# Medir-220.net
KiCad netlist of a schematic drawn in EAGLE
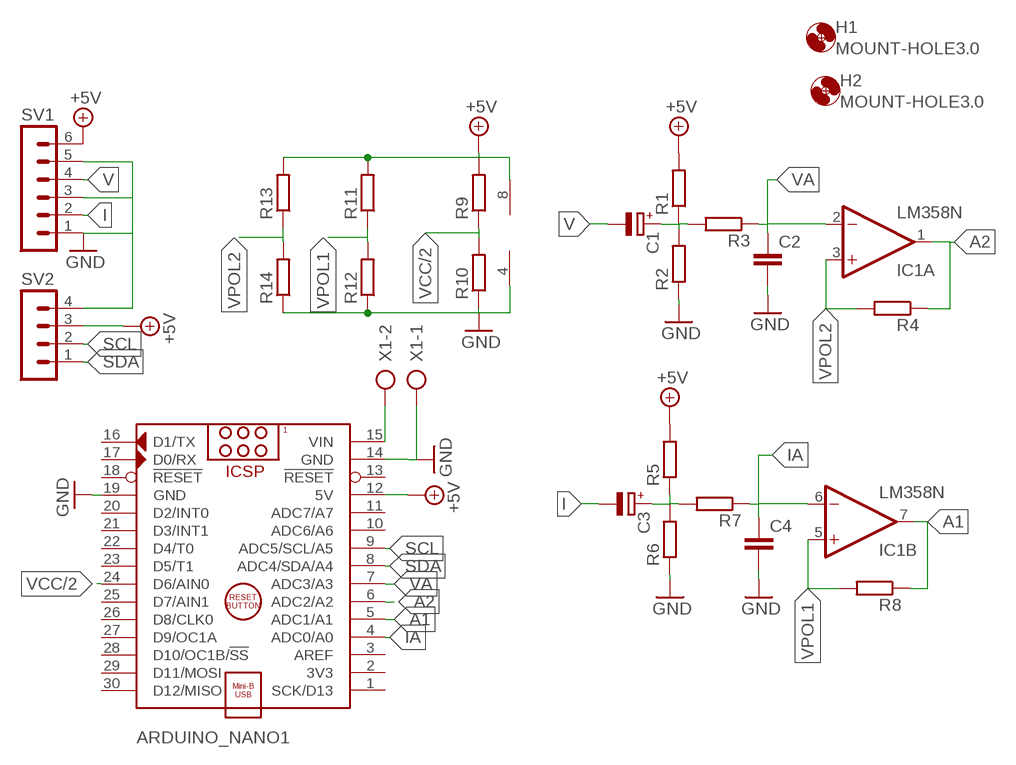
[diagram p0: schematic, sheet 1]

(export (version "E")
  (design (tool "Eeschema 10.0.6"))
  (components
    (comp (ref "ARDUINO_NANO1")
      (value "ARDUINO_NANO")
      (footprint "eagle-import:ARDUINO_NANO")
      (libsource (lib "eagle-import") (part "ARDUINO_NANO"))
    )
    (comp (ref "C1")
      (value "CPOL-EUE2.5-5")
      (footprint "eagle-import:E2,5-5")
      (libsource (lib "eagle-import") (part "CPOL-EUE2.5-5"))
    )
    (comp (ref "C2")
      (value "C-EU050-025X075")
      (footprint "eagle-import:C050-025X075")
      (libsource (lib "eagle-import") (part "C-EU050-025X075"))
    )
    (comp (ref "C3")
      (value "CPOL-EUE2.5-5")
      (footprint "eagle-import:E2,5-5")
      (libsource (lib "eagle-import") (part "CPOL-EUE2.5-5"))
    )
    (comp (ref "C4")
      (value "C-EU050-025X075")
      (footprint "eagle-import:C050-025X075")
      (libsource (lib "eagle-import") (part "C-EU050-025X075"))
    )
    (comp (ref "H1")
      (value "MOUNT-HOLE3.0")
      (footprint "eagle-import:3,0")
      (libsource (lib "eagle-import") (part "MOUNT-HOLE3.0"))
    )
    (comp (ref "H2")
      (value "MOUNT-HOLE3.0")
      (footprint "eagle-import:3,0")
      (libsource (lib "eagle-import") (part "MOUNT-HOLE3.0"))
    )
    (comp (ref "IC1")
      (value "LM358N")
      (footprint "eagle-import:DIL08")
      (libsource (lib "eagle-import") (part "LM358N"))
    )
    (comp (ref "R1")
      (value "R-EU_0207/7")
      (footprint "eagle-import:0207_7")
      (libsource (lib "eagle-import") (part "resistor_R-EU_0207/7"))
    )
    (comp (ref "R2")
      (value "R-EU_0207/7")
      (footprint "eagle-import:0207_7")
      (libsource (lib "eagle-import") (part "resistor_R-EU_0207/7"))
    )
    (comp (ref "R3")
      (value "R-EU_0207/7")
      (footprint "eagle-import:0207_7")
      (libsource (lib "eagle-import") (part "resistor_R-EU_0207/7"))
    )
    (comp (ref "R4")
      (value "R-EU_0207/7")
      (footprint "eagle-import:0207_7")
      (libsource (lib "eagle-import") (part "resistor_R-EU_0207/7"))
    )
    (comp (ref "R5")
      (value "R-EU_0207/7")
      (footprint "eagle-import:0207_7")
      (libsource (lib "eagle-import") (part "resistor_R-EU_0207/7"))
    )
    (comp (ref "R6")
      (value "R-EU_0207/7")
      (footprint "eagle-import:0207_7")
      (libsource (lib "eagle-import") (part "resistor_R-EU_0207/7"))
    )
    (comp (ref "R7")
      (value "R-EU_0207/7")
      (footprint "eagle-import:0207_7")
      (libsource (lib "eagle-import") (part "resistor_R-EU_0207/7"))
    )
    (comp (ref "R8")
      (value "R-EU_0207/7")
      (footprint "eagle-import:0207_7")
      (libsource (lib "eagle-import") (part "resistor_R-EU_0207/7"))
    )
    (comp (ref "R9")
      (value "R-EU_0207/10")
      (footprint "eagle-import:0207_10")
      (libsource (lib "eagle-import") (part "R-EU_0207/10"))
    )
    (comp (ref "R10")
      (value "R-EU_0207/10")
      (footprint "eagle-import:0207_10")
      (libsource (lib "eagle-import") (part "R-EU_0207/10"))
    )
    (comp (ref "R11")
      (value "R-EU_0207/7")
      (footprint "eagle-import:0207_7")
      (libsource (lib "eagle-import") (part "resistor_R-EU_0207/7"))
    )
    (comp (ref "R12")
      (value "R-EU_0207/7")
      (footprint "eagle-import:0207_7")
      (libsource (lib "eagle-import") (part "resistor_R-EU_0207/7"))
    )
    (comp (ref "R13")
      (value "R-EU_0207/7")
      (footprint "eagle-import:0207_7")
      (libsource (lib "eagle-import") (part "resistor_R-EU_0207/7"))
    )
    (comp (ref "R14")
      (value "R-EU_0207/7")
      (footprint "eagle-import:0207_7")
      (libsource (lib "eagle-import") (part "resistor_R-EU_0207/7"))
    )
    (comp (ref "SV1")
      (value "MA06-1")
      (footprint "eagle-import:MA06-1")
      (libsource (lib "eagle-import") (part "MA06-1"))
    )
    (comp (ref "SV2")
      (value "MA04-1")
      (footprint "eagle-import:MA04-1")
      (libsource (lib "eagle-import") (part "MA04-1"))
    )
    (comp (ref "X1")
      (value "AK500/2")
      (footprint "eagle-import:AK500_2")
      (libsource (lib "eagle-import") (part "AK500/2"))
    )
  )
  (nets
    (net (code "1") (name "+5V") (class "Default")
      (node (ref "ARDUINO_NANO1") (pin "12") (pinfunction "5V_12") (pintype "power_in"))
      (node (ref "IC1") (pin "8") (pinfunction "V+_8") (pintype "power_in"))
      (node (ref "R1") (pin "2") (pinfunction "2_2") (pintype "passive"))
      (node (ref "R11") (pin "2") (pinfunction "2_2") (pintype "passive"))
      (node (ref "R13") (pin "2") (pinfunction "2_2") (pintype "passive"))
      (node (ref "R5") (pin "2") (pinfunction "2_2") (pintype "passive"))
      (node (ref "R9") (pin "2") (pinfunction "2_2") (pintype "passive"))
      (node (ref "SV1") (pin "6") (pinfunction "6_6") (pintype "passive"))
      (node (ref "SV2") (pin "3") (pinfunction "3_3") (pintype "passive"))
    )
    (net (code "2") (name "A1") (class "Default")
      (node (ref "ARDUINO_NANO1") (pin "5") (pinfunction "ADC1/A1_5") (pintype "bidirectional"))
      (node (ref "IC1") (pin "7") (pinfunction "OUT_7") (pintype "output"))
      (node (ref "R8") (pin "1") (pinfunction "1_1") (pintype "passive"))
    )
    (net (code "3") (name "A2") (class "Default")
      (node (ref "ARDUINO_NANO1") (pin "6") (pinfunction "ADC2/A2_6") (pintype "bidirectional"))
      (node (ref "IC1") (pin "1") (pinfunction "OUT_1") (pintype "output"))
      (node (ref "R4") (pin "1") (pinfunction "1_1") (pintype "passive"))
    )
    (net (code "4") (name "GND") (class "Default")
      (node (ref "ARDUINO_NANO1") (pin "14") (pinfunction "GND_14") (pintype "power_in"))
      (node (ref "ARDUINO_NANO1") (pin "19") (pinfunction "GND_19") (pintype "power_in"))
      (node (ref "C2") (pin "2") (pinfunction "2_2") (pintype "passive"))
      (node (ref "C4") (pin "2") (pinfunction "2_2") (pintype "passive"))
      (node (ref "IC1") (pin "4") (pinfunction "V-_4") (pintype "power_in"))
      (node (ref "R10") (pin "1") (pinfunction "1_1") (pintype "passive"))
      (node (ref "R12") (pin "1") (pinfunction "1_1") (pintype "passive"))
      (node (ref "R14") (pin "1") (pinfunction "1_1") (pintype "passive"))
      (node (ref "R2") (pin "1") (pinfunction "1_1") (pintype "passive"))
      (node (ref "R6") (pin "1") (pinfunction "1_1") (pintype "passive"))
      (node (ref "SV1") (pin "1") (pinfunction "1_1") (pintype "passive"))
      (node (ref "SV1") (pin "3") (pinfunction "3_3") (pintype "passive"))
      (node (ref "SV1") (pin "5") (pinfunction "5_5") (pintype "passive"))
      (node (ref "SV2") (pin "4") (pinfunction "4_4") (pintype "passive"))
      (node (ref "X1") (pin "1") (pinfunction "KL_1") (pintype "passive"))
    )
    (net (code "5") (name "I") (class "Default")
      (node (ref "C3") (pin "-") (pinfunction "-_-") (pintype "passive"))
      (node (ref "SV1") (pin "2") (pinfunction "2_2") (pintype "passive"))
    )
    (net (code "6") (name "IA") (class "Default")
      (node (ref "ARDUINO_NANO1") (pin "4") (pinfunction "ADC0/A0_4") (pintype "bidirectional"))
      (node (ref "C4") (pin "1") (pinfunction "1_1") (pintype "passive"))
      (node (ref "IC1") (pin "6") (pinfunction "-IN_6") (pintype "input"))
      (node (ref "R7") (pin "1") (pinfunction "1_1") (pintype "passive"))
    )
    (net (code "7") (name "Net-(ARDUINO_NANO1-VIN)") (class "Default")
      (node (ref "ARDUINO_NANO1") (pin "15") (pinfunction "VIN_15") (pintype "power_in"))
      (node (ref "X1") (pin "2") (pinfunction "KL_2") (pintype "passive"))
    )
    (net (code "8") (name "Net-(C1-Pad+)") (class "Default")
      (node (ref "C1") (pin "+") (pinfunction "+_+") (pintype "passive"))
      (node (ref "R1") (pin "1") (pinfunction "1_1") (pintype "passive"))
      (node (ref "R2") (pin "2") (pinfunction "2_2") (pintype "passive"))
      (node (ref "R3") (pin "2") (pinfunction "2_2") (pintype "passive"))
    )
    (net (code "9") (name "Net-(C3-Pad+)") (class "Default")
      (node (ref "C3") (pin "+") (pinfunction "+_+") (pintype "passive"))
      (node (ref "R5") (pin "1") (pinfunction "1_1") (pintype "passive"))
      (node (ref "R6") (pin "2") (pinfunction "2_2") (pintype "passive"))
      (node (ref "R7") (pin "2") (pinfunction "2_2") (pintype "passive"))
    )
    (net (code "10") (name "SCL") (class "Default")
      (node (ref "ARDUINO_NANO1") (pin "9") (pinfunction "ADC5/SCL/A5_9") (pintype "bidirectional"))
      (node (ref "SV2") (pin "2") (pinfunction "2_2") (pintype "passive"))
    )
    (net (code "11") (name "SDA") (class "Default")
      (node (ref "ARDUINO_NANO1") (pin "8") (pinfunction "ADC4/SDA/A4_8") (pintype "bidirectional"))
      (node (ref "SV2") (pin "1") (pinfunction "1_1") (pintype "passive"))
    )
    (net (code "12") (name "V") (class "Default")
      (node (ref "C1") (pin "-") (pinfunction "-_-") (pintype "passive"))
      (node (ref "SV1") (pin "4") (pinfunction "4_4") (pintype "passive"))
    )
    (net (code "13") (name "VA") (class "Default")
      (node (ref "ARDUINO_NANO1") (pin "7") (pinfunction "ADC3/A3_7") (pintype "bidirectional"))
      (node (ref "C2") (pin "1") (pinfunction "1_1") (pintype "passive"))
      (node (ref "IC1") (pin "2") (pinfunction "-IN_2") (pintype "input"))
      (node (ref "R3") (pin "1") (pinfunction "1_1") (pintype "passive"))
    )
    (net (code "14") (name "VCC{slash}2") (class "Default")
      (node (ref "ARDUINO_NANO1") (pin "24") (pinfunction "D6/AIN0_24") (pintype "bidirectional"))
      (node (ref "R10") (pin "2") (pinfunction "2_2") (pintype "passive"))
      (node (ref "R9") (pin "1") (pinfunction "1_1") (pintype "passive"))
    )
    (net (code "15") (name "VPOL1") (class "Default")
      (node (ref "IC1") (pin "5") (pinfunction "+IN_5") (pintype "input"))
      (node (ref "R11") (pin "1") (pinfunction "1_1") (pintype "passive"))
      (node (ref "R12") (pin "2") (pinfunction "2_2") (pintype "passive"))
      (node (ref "R8") (pin "2") (pinfunction "2_2") (pintype "passive"))
    )
    (net (code "16") (name "VPOL2") (class "Default")
      (node (ref "IC1") (pin "3") (pinfunction "+IN_3") (pintype "input"))
      (node (ref "R13") (pin "1") (pinfunction "1_1") (pintype "passive"))
      (node (ref "R14") (pin "2") (pinfunction "2_2") (pintype "passive"))
      (node (ref "R4") (pin "2") (pinfunction "2_2") (pintype "passive"))
    )
    (net (code "17") (name "unconnected-(ARDUINO_NANO1-3V3-Pad2)") (class "Default")
      (node (ref "ARDUINO_NANO1") (pin "2") (pinfunction "3V3_2") (pintype "output"))
    )
    (net (code "18") (name "unconnected-(ARDUINO_NANO1-ADC6{slash}A6-Pad10)") (class "Default")
      (node (ref "ARDUINO_NANO1") (pin "10") (pinfunction "ADC6/A6_10") (pintype "bidirectional"))
    )
    (net (code "19") (name "unconnected-(ARDUINO_NANO1-ADC7{slash}A7-Pad11)") (class "Default")
      (node (ref "ARDUINO_NANO1") (pin "11") (pinfunction "ADC7/A7_11") (pintype "bidirectional"))
    )
    (net (code "20") (name "unconnected-(ARDUINO_NANO1-AREF-Pad3)") (class "Default")
      (node (ref "ARDUINO_NANO1") (pin "3") (pinfunction "AREF_3") (pintype "input"))
    )
    (net (code "21") (name "unconnected-(ARDUINO_NANO1-D0{slash}RX-Pad17)") (class "Default")
      (node (ref "ARDUINO_NANO1") (pin "17") (pinfunction "D0/RX_17") (pintype "bidirectional"))
    )
    (net (code "22") (name "unconnected-(ARDUINO_NANO1-D1{slash}TX-Pad16)") (class "Default")
      (node (ref "ARDUINO_NANO1") (pin "16") (pinfunction "D1/TX_16") (pintype "bidirectional"))
    )
    (net (code "23") (name "unconnected-(ARDUINO_NANO1-D2{slash}INT0-Pad20)") (class "Default")
      (node (ref "ARDUINO_NANO1") (pin "20") (pinfunction "D2/INT0_20") (pintype "bidirectional"))
    )
    (net (code "24") (name "unconnected-(ARDUINO_NANO1-D3{slash}INT1-Pad21)") (class "Default")
      (node (ref "ARDUINO_NANO1") (pin "21") (pinfunction "D3/INT1_21") (pintype "bidirectional"))
    )
    (net (code "25") (name "unconnected-(ARDUINO_NANO1-D4{slash}T0-Pad22)") (class "Default")
      (node (ref "ARDUINO_NANO1") (pin "22") (pinfunction "D4/T0_22") (pintype "bidirectional"))
    )
    (net (code "26") (name "unconnected-(ARDUINO_NANO1-D5{slash}T1-Pad23)") (class "Default")
      (node (ref "ARDUINO_NANO1") (pin "23") (pinfunction "D5/T1_23") (pintype "bidirectional"))
    )
    (net (code "27") (name "unconnected-(ARDUINO_NANO1-D7{slash}AIN1-Pad25)") (class "Default")
      (node (ref "ARDUINO_NANO1") (pin "25") (pinfunction "D7/AIN1_25") (pintype "bidirectional"))
    )
    (net (code "28") (name "unconnected-(ARDUINO_NANO1-D8{slash}CLK0-Pad26)") (class "Default")
      (node (ref "ARDUINO_NANO1") (pin "26") (pinfunction "D8/CLK0_26") (pintype "bidirectional"))
    )
    (net (code "29") (name "unconnected-(ARDUINO_NANO1-D9{slash}OC1A-Pad27)") (class "Default")
      (node (ref "ARDUINO_NANO1") (pin "27") (pinfunction "D9/OC1A_27") (pintype "bidirectional"))
    )
    (net (code "30") (name "unconnected-(ARDUINO_NANO1-D10{slash}OC1B{slash}~{SS}-Pad28)") (class "Default")
      (node (ref "ARDUINO_NANO1") (pin "28") (pinfunction "D10/OC1B/~{SS}_28") (pintype "bidirectional"))
    )
    (net (code "31") (name "unconnected-(ARDUINO_NANO1-D11{slash}MOSI-Pad29)") (class "Default")
      (node (ref "ARDUINO_NANO1") (pin "29") (pinfunction "D11/MOSI_29") (pintype "bidirectional"))
    )
    (net (code "32") (name "unconnected-(ARDUINO_NANO1-D12{slash}MISO-Pad30)") (class "Default")
      (node (ref "ARDUINO_NANO1") (pin "30") (pinfunction "D12/MISO_30") (pintype "bidirectional"))
    )
    (net (code "33") (name "unconnected-(ARDUINO_NANO1-SCK{slash}D13-Pad1)") (class "Default")
      (node (ref "ARDUINO_NANO1") (pin "1") (pinfunction "SCK/D13_1") (pintype "bidirectional"))
    )
    (net (code "34") (name "unconnected-(ARDUINO_NANO1-~{RESET}-Pad13)") (class "Default")
      (node (ref "ARDUINO_NANO1") (pin "13") (pinfunction "~{RESET}_13") (pintype "input"))
    )
    (net (code "35") (name "unconnected-(ARDUINO_NANO1-~{RESET}-Pad18)") (class "Default")
      (node (ref "ARDUINO_NANO1") (pin "18") (pinfunction "~{RESET}_18") (pintype "input"))
    )
  )
)
